# 2_Input_Signal_Conditioner.net
KiCad netlist of a schematic drawn in Altium Designer
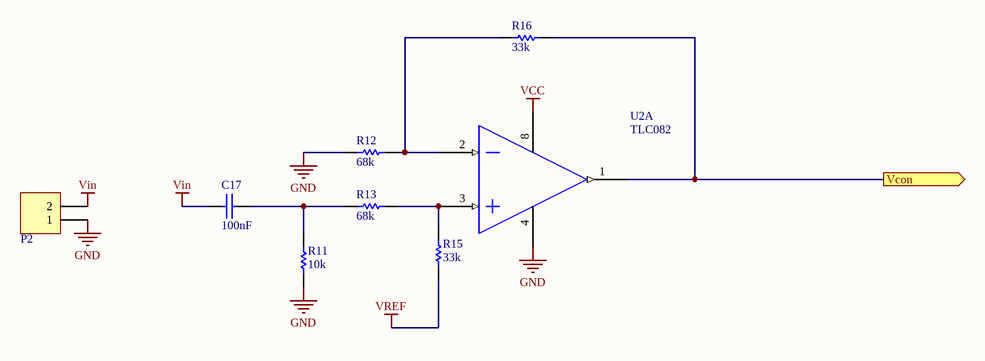
[diagram p0: 2_Input Signal Conditioner.SchDoc]

(export (version "E")
  (design (tool "Eeschema 10.0.6"))
  (components
    (comp (ref "C17")
      (value "100nF")
      (footprint "ece-RAD0.2")
      (description "Capacitor Non Polarised Through Hole")
      (libsource (lib "ece components") (part "CAP"))
    )
    (comp (ref "P2")
      (value "Header 2")
      (footprint "ece-TER2-10MM")
      (description "Large 2 way screw connector")
      (libsource (lib "ece components") (part "TERMINAL 2"))
    )
    (comp (ref "R11")
      (value "10k")
      (footprint "ece-AXIAL0.4")
      (description "Resistor")
      (fields (field (name "PUBLISHER") "Altium Limited"))
      (libsource (lib "ece components") (part "Res1"))
    )
    (comp (ref "R12")
      (value "68k")
      (footprint "ece-AXIAL0.4")
      (description "Resistor")
      (fields (field (name "PUBLISHER") "Altium Limited"))
      (libsource (lib "ece components") (part "Res1"))
    )
    (comp (ref "R13")
      (value "68k")
      (footprint "ece-AXIAL0.4")
      (description "Resistor")
      (fields (field (name "PUBLISHER") "Altium Limited"))
      (libsource (lib "ece components") (part "Res1"))
    )
    (comp (ref "R15")
      (value "33k")
      (footprint "ece-AXIAL0.4")
      (description "Resistor")
      (fields (field (name "PUBLISHER") "Altium Limited"))
      (libsource (lib "ece components") (part "Res1"))
    )
    (comp (ref "R16")
      (value "33k")
      (footprint "ece-AXIAL0.4")
      (description "Resistor")
      (fields (field (name "PUBLISHER") "Altium Limited"))
      (libsource (lib "ece components") (part "Res1"))
    )
    (comp (ref "U2")
      (value "TLC082")
      (footprint "ECE-DIP8")
      (libsource (lib "ece components") (part "TLC082"))
    )
  )
  (nets
    (net (code "1") (name "/Vcon") (class "Default")
      (node (ref "R16") (pin "1") (pinfunction "1_1") (pintype "passive"))
      (node (ref "U2") (pin "1") (pinfunction "OUT1_1") (pintype "output"))
    )
    (net (code "2") (name "GND") (class "Default")
      (node (ref "P2") (pin "1") (pinfunction "1_1") (pintype "passive"))
      (node (ref "R11") (pin "1") (pinfunction "1_1") (pintype "passive"))
      (node (ref "R12") (pin "2") (pinfunction "2_2") (pintype "passive"))
      (node (ref "U2") (pin "4") (pinfunction "GND_4") (pintype "power_in"))
    )
    (net (code "3") (name "Net-(C17-Pad2)") (class "Default")
      (node (ref "C17") (pin "2") (pinfunction "2_2") (pintype "passive"))
      (node (ref "R11") (pin "2") (pinfunction "2_2") (pintype "passive"))
      (node (ref "R13") (pin "2") (pinfunction "2_2") (pintype "passive"))
    )
    (net (code "4") (name "Net-(U2A-IN1(+))") (class "Default")
      (node (ref "R13") (pin "1") (pinfunction "1_1") (pintype "passive"))
      (node (ref "R15") (pin "2") (pinfunction "2_2") (pintype "passive"))
      (node (ref "U2") (pin "3") (pinfunction "IN1(+)_3") (pintype "input"))
    )
    (net (code "5") (name "Net-(U2A-IN1(-))") (class "Default")
      (node (ref "R12") (pin "1") (pinfunction "1_1") (pintype "passive"))
      (node (ref "R16") (pin "2") (pinfunction "2_2") (pintype "passive"))
      (node (ref "U2") (pin "2") (pinfunction "IN1(-)_2") (pintype "input"))
    )
    (net (code "6") (name "VCC") (class "Default")
      (node (ref "U2") (pin "8") (pinfunction "V(+)_8") (pintype "power_in"))
    )
    (net (code "7") (name "VREF") (class "Default")
      (node (ref "R15") (pin "1") (pinfunction "1_1") (pintype "passive"))
    )
    (net (code "8") (name "Vin") (class "Default")
      (node (ref "C17") (pin "1") (pinfunction "1_1") (pintype "passive"))
      (node (ref "P2") (pin "2") (pinfunction "2_2") (pintype "passive"))
    )
  )
)
